# 013_BP.net
KiCad netlist of a schematic drawn in Altium Designer
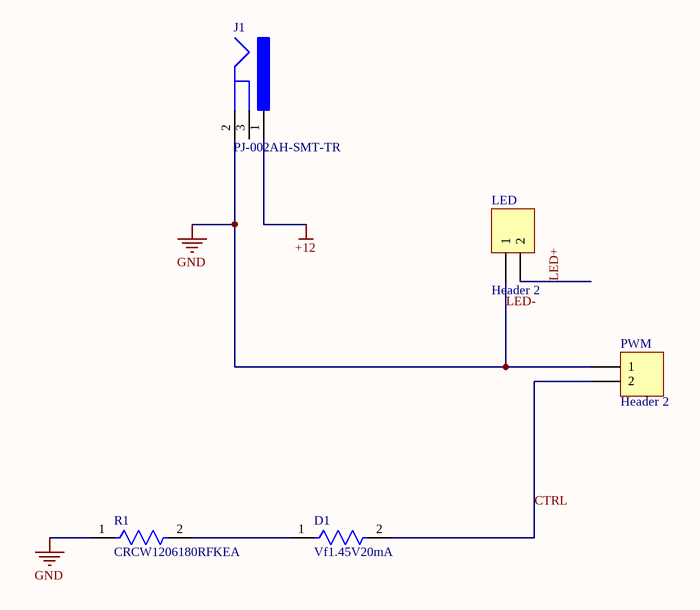
[diagram p0: 013_BP.SchDoc]

(export (version "E")
  (design (tool "Eeschema 10.0.6"))
  (components
    (comp (ref "D1")
      (value "Vf1.45V20mA")
      (footprint "FP-CRCW1206-e3-IPC_C")
      (description "RES Thick Film, 180Ω, 1%, 0.25W, 100ppm/°C, 1206")
      (fields (field (name "TOLERANCE") "1%"))
      (libsource (lib "Altium Content Vault") (part "1029c3af85768c4190bb7ad29bc67b5"))
    )
    (comp (ref "J1")
      (value "PJ-002AH-SMT-TR")
      (footprint "CUI-PJ-002AH-4_V")
      (description "DC Power Jack, Right Angle, -25 to 85 degC, 4-Pin 14.8 x 9 x 11 mm SMD, RoHS, Tape and Reel")
      (fields (field (name "MANUFACTURER") "CUIInc.") (field (name "PARTNUMBER") "PJ-002AH"))
      (libsource (lib "Altium Content Vault") (part "JACK-2CD3-RN_B"))
    )
    (comp (ref "LED")
      (value "Header 2")
      (footprint "HDR1X2")
      (description "Header, 2-Pin")
      (fields (field (name "PUBLISHER") "Altium Limited"))
      (libsource (lib "Miscellaneous Connectors") (part "Header 2"))
    )
    (comp (ref "PWM")
      (value "Header 2")
      (footprint "HDR1X2")
      (description "Header, 2-Pin")
      (fields (field (name "PUBLISHER") "Altium Limited"))
      (libsource (lib "") (part "Header 2_1"))
    )
    (comp (ref "R1")
      (value "CRCW1206180RFKEA")
      (footprint "FP-CRCW1206-e3-IPC_C")
      (description "RES Thick Film, 180Ω, 1%, 0.25W, 100ppm/°C, 1206")
      (fields (field (name "TOLERANCE") "1%"))
      (libsource (lib "Altium Content Vault") (part "1029c3af85768c4190bb7ad29bc67b5"))
    )
  )
  (nets
    (net (code "1") (name "+12") (class "Default")
      (node (ref "J1") (pin "1") (pinfunction "1_1") (pintype "passive"))
    )
    (net (code "2") (name "/CTRL") (class "Default")
      (node (ref "D1") (pin "2") (pinfunction "2_2") (pintype "passive"))
      (node (ref "PWM") (pin "2") (pinfunction "2_2") (pintype "passive"))
    )
    (net (code "3") (name "/LED+") (class "Default")
      (node (ref "LED") (pin "2") (pinfunction "2_2") (pintype "passive"))
    )
    (net (code "4") (name "GND") (class "Default")
      (node (ref "J1") (pin "2") (pinfunction "2_2") (pintype "passive"))
      (node (ref "LED") (pin "1") (pinfunction "1_1") (pintype "passive"))
      (node (ref "PWM") (pin "1") (pinfunction "1_1") (pintype "passive"))
      (node (ref "R1") (pin "1") (pinfunction "1_1") (pintype "passive"))
    )
    (net (code "5") (name "Net-(D1-Pad1)") (class "Default")
      (node (ref "D1") (pin "1") (pinfunction "1_1") (pintype "passive"))
      (node (ref "R1") (pin "2") (pinfunction "2_2") (pintype "passive"))
    )
    (net (code "6") (name "unconnected-(J1-Pad3)") (class "Default")
      (node (ref "J1") (pin "3") (pinfunction "3_3") (pintype "passive"))
    )
  )
)
